# Smart_shoe_Power.net
KiCad netlist of a schematic drawn in Altium Designer
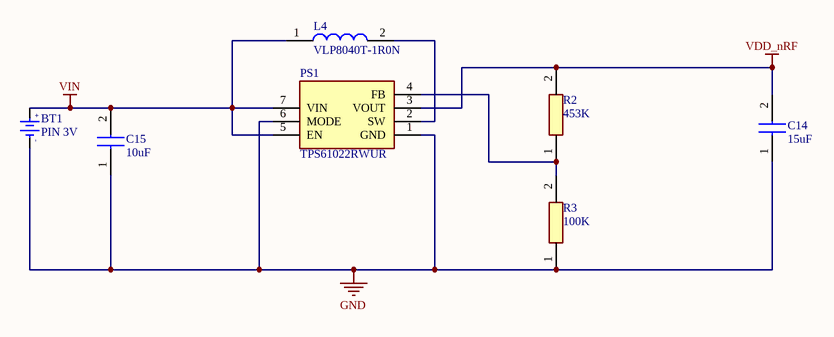
[diagram p0: Smart shoe_Power.SchDoc]

(export (version "E")
  (design (tool "Eeschema 10.0.6"))
  (components
    (comp (ref "BT1")
      (value "PIN 3V")
      (footprint "PIN3V")
      (description "Battery 3VDC")
      (libsource (lib "syhaunguyen") (part "PIN 3V"))
    )
    (comp (ref "C14")
      (value "15uF")
      (footprint "CAPC2012X145N")
      (description "Capacitor")
      (fields
        (field (name "MANUFACTURER_PART_NUMBER") "C2012X5R1V156M125AC")
        (field (name "MOUSER PART NUMBER") "810-C2012X5R1V156M1C")
      )
      (libsource (lib "*") (part "C2012X5R1V156M125AC"))
    )
    (comp (ref "C15")
      (value "10uF")
      (footprint "CAPC2012X145N")
      (description "Capacitor")
      (fields
        (field (name "MANUFACTURER_PART_NUMBER") "C0805C106K8PACTU")
        (field (name "MOUSER PART NUMBER") "80-C0805C106K8P")
      )
      (libsource (lib "*") (part "C0805C106K8PACTU"))
    )
    (comp (ref "L4")
      (value "VLP8040T-1R0N")
      (footprint "SamacSys:VLP8040T_1")
      (description "Inductor")
      (fields (field (name "MOUSER PART NUMBER") "810-VLP8040T-1R0N"))
      (libsource (lib "SamacSys") (part "VLP8040T-1R0N"))
    )
    (comp (ref "PS1")
      (value "TPS61022RWUR")
      (footprint "TPS61022RWUR")
      (description "Power Supply")
      (fields (field (name "MOUSER PART NUMBER") "595-TPS61022RWUR"))
      (libsource (lib "*") (part "TPS61022RWUR"))
    )
    (comp (ref "R2")
      (value "453K")
      (footprint "SamacSys:RESC1005X40N")
      (description "Resistor")
      (fields
        (field (name "MANUFACTURER_PART_NUMBER") "CRCW0402453KFKED")
        (field (name "MOUSER PART NUMBER") "71-CRCW0402-453K-E3")
      )
      (libsource (lib "*") (part "CRCW0402453KFKED"))
    )
    (comp (ref "R3")
      (value "100K")
      (footprint "SamacSys:RESC1005X40N")
      (description "Resistor")
      (fields
        (field (name "MANUFACTURER_PART_NUMBER") "CRCW0402100KFKEDHP")
        (field (name "MOUSER PART NUMBER") "71-CRCW0402100KFKEDH")
      )
      (libsource (lib "*") (part "CRCW0402100KFKEDHP"))
    )
  )
  (nets
    (net (code "1") (name "GND") (class "Default")
      (node (ref "BT1") (pin "2") (pinfunction "GND_2") (pintype "passive"))
      (node (ref "C14") (pin "1") (pinfunction "1_1") (pintype "passive"))
      (node (ref "C15") (pin "1") (pinfunction "1_1") (pintype "passive"))
      (node (ref "PS1") (pin "1") (pinfunction "GND_1") (pintype "passive"))
      (node (ref "PS1") (pin "6") (pinfunction "MODE_6") (pintype "passive"))
      (node (ref "R3") (pin "1") (pinfunction "1_1") (pintype "passive"))
    )
    (net (code "2") (name "Net-(PS1-FB)") (class "Default")
      (node (ref "PS1") (pin "4") (pinfunction "FB_4") (pintype "passive"))
      (node (ref "R2") (pin "1") (pinfunction "1_1") (pintype "passive"))
      (node (ref "R3") (pin "2") (pinfunction "2_2") (pintype "passive"))
    )
    (net (code "3") (name "Net-(PS1-SW)") (class "Default")
      (node (ref "L4") (pin "2") (pinfunction "2_2") (pintype "passive"))
      (node (ref "PS1") (pin "2") (pinfunction "SW_2") (pintype "passive"))
    )
    (net (code "4") (name "VDD_nRF") (class "Default")
      (node (ref "C14") (pin "2") (pinfunction "2_2") (pintype "passive"))
      (node (ref "PS1") (pin "3") (pinfunction "VOUT_3") (pintype "passive"))
      (node (ref "R2") (pin "2") (pinfunction "2_2") (pintype "passive"))
    )
    (net (code "5") (name "VIN") (class "Default")
      (node (ref "BT1") (pin "1") (pinfunction "+3V_1") (pintype "passive"))
      (node (ref "C15") (pin "2") (pinfunction "2_2") (pintype "passive"))
      (node (ref "L4") (pin "1") (pinfunction "1_1") (pintype "passive"))
      (node (ref "PS1") (pin "5") (pinfunction "EN_5") (pintype "passive"))
      (node (ref "PS1") (pin "7") (pinfunction "VIN_7") (pintype "passive"))
    )
  )
)
